# controller_board.net
KiCad netlist of a schematic drawn in EAGLE
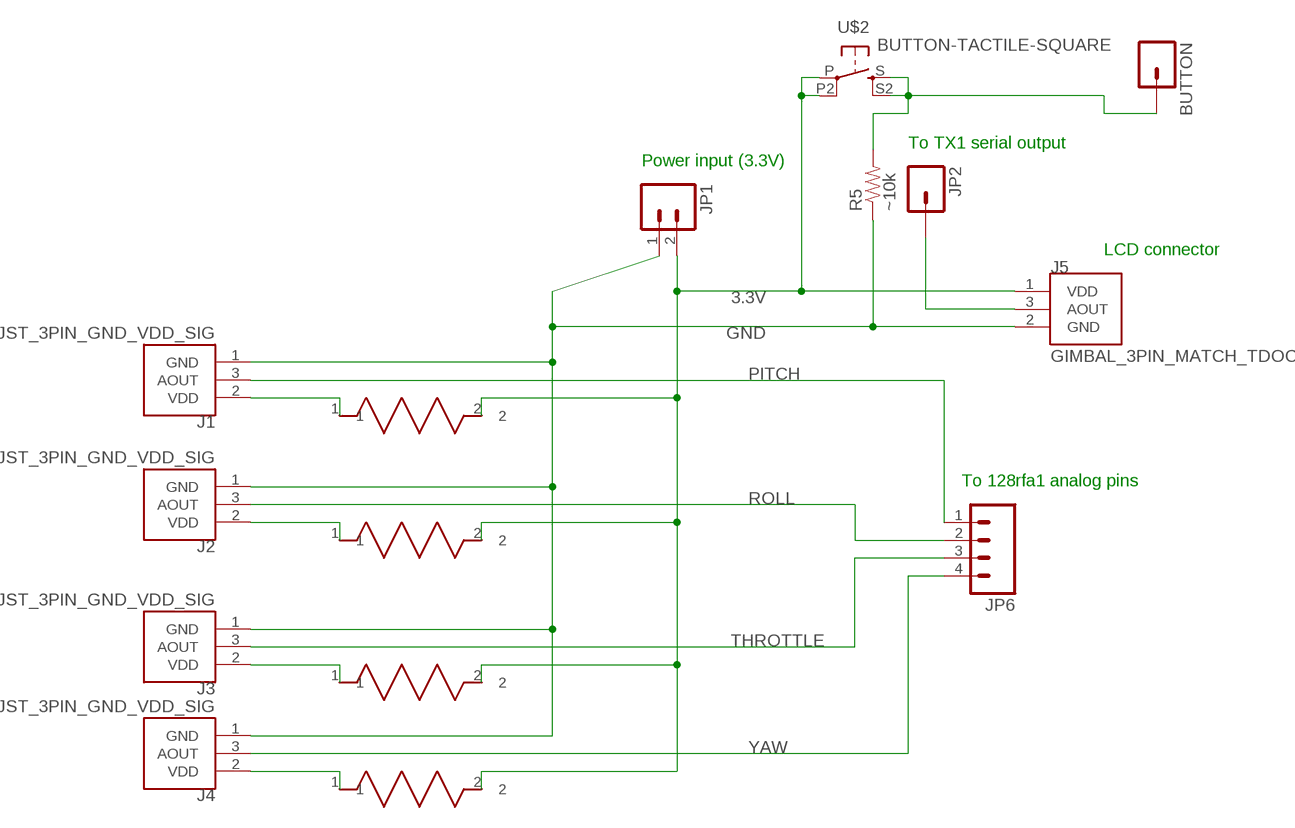
[diagram p0: schematic, sheet 1]

(export (version "E")
  (design (tool "Eeschema 10.0.6"))
  (components
    (comp (ref "BUTTON")
      (value "M01PTH")
      (footprint "eagle-import:1X01")
      (libsource (lib "eagle-import") (part "M01PTH"))
    )
    (comp (ref "J1")
      (value "JST_3PIN_GND_VDD_SIG")
      (footprint "eagle-import:JST-3-PTH-REVERSE")
      (libsource (lib "eagle-import") (part "JST_3PIN_GND_VDD_SIG"))
    )
    (comp (ref "J2")
      (value "JST_3PIN_GND_VDD_SIG")
      (footprint "eagle-import:JST-3-PTH-REVERSE")
      (libsource (lib "eagle-import") (part "JST_3PIN_GND_VDD_SIG"))
    )
    (comp (ref "J3")
      (value "JST_3PIN_GND_VDD_SIG")
      (footprint "eagle-import:JST-3-PTH-REVERSE")
      (libsource (lib "eagle-import") (part "JST_3PIN_GND_VDD_SIG"))
    )
    (comp (ref "J4")
      (value "JST_3PIN_GND_VDD_SIG")
      (footprint "eagle-import:JST-3-PTH-REVERSE")
      (libsource (lib "eagle-import") (part "JST_3PIN_GND_VDD_SIG"))
    )
    (comp (ref "J5")
      (value "GIMBAL_3PIN_MATCH_TDOCU")
      (footprint "eagle-import:JST-3-PTH")
      (libsource (lib "eagle-import") (part "GIMBAL_3PIN_MATCH_TDOCU"))
    )
    (comp (ref "JP1")
      (value "M021X02_NO_SILK")
      (footprint "eagle-import:1X02_NO_SILK")
      (libsource (lib "eagle-import") (part "M021X02_NO_SILK"))
    )
    (comp (ref "JP2")
      (value "M01PTH")
      (footprint "eagle-import:1X01")
      (libsource (lib "eagle-import") (part "M01PTH"))
    )
    (comp (ref "JP6")
      (value "M04PTH")
      (footprint "eagle-import:1X04")
      (libsource (lib "eagle-import") (part "M04PTH"))
    )
    (comp (ref "PITCH")
      (value "2.5k")
      (footprint "eagle-import:RES_CRF12")
      (libsource (lib "eagle-import") (part "RES_CRF12"))
    )
    (comp (ref "R5")
      (value "~10k")
      (footprint "eagle-import:AXIAL-0.4")
      (libsource (lib "eagle-import") (part "RESISTORPTH-1/4W"))
    )
    (comp (ref "ROLL")
      (value "2.5k")
      (footprint "eagle-import:RES_CRF12")
      (libsource (lib "eagle-import") (part "RES_CRF12"))
    )
    (comp (ref "THROTTLE")
      (value "2.5k")
      (footprint "eagle-import:RES_CRF12")
      (libsource (lib "eagle-import") (part "RES_CRF12"))
    )
    (comp (ref "U$2")
      (value "BUTTON-TACTILE-SQUARE")
      (footprint "eagle-import:BUTTON-TACTILE-SQUARE-ADAFRUIT1010")
      (libsource (lib "eagle-import") (part "BUTTON-TACTILE-SQUARE"))
    )
    (comp (ref "YAW")
      (value "2.5k")
      (footprint "eagle-import:RES_CRF12")
      (libsource (lib "eagle-import") (part "RES_CRF12"))
    )
  )
  (nets
    (net (code "1") (name "/3.3V") (class "Default")
      (node (ref "J5") (pin "1") (pinfunction "VDD_1") (pintype "power_in"))
      (node (ref "JP1") (pin "2") (pinfunction "2_2") (pintype "passive"))
      (node (ref "PITCH") (pin "2") (pinfunction "2_2") (pintype "bidirectional"))
      (node (ref "ROLL") (pin "2") (pinfunction "2_2") (pintype "bidirectional"))
      (node (ref "THROTTLE") (pin "2") (pinfunction "2_2") (pintype "bidirectional"))
      (node (ref "U$2") (pin "P") (pinfunction "P_P") (pintype "passive"))
      (node (ref "U$2") (pin "P2") (pinfunction "P1_P2") (pintype "passive"))
      (node (ref "YAW") (pin "2") (pinfunction "2_2") (pintype "bidirectional"))
    )
    (net (code "2") (name "/GND") (class "Default")
      (node (ref "J1") (pin "1") (pinfunction "GND_1") (pintype "power_in"))
      (node (ref "J2") (pin "1") (pinfunction "GND_1") (pintype "power_in"))
      (node (ref "J3") (pin "1") (pinfunction "GND_1") (pintype "power_in"))
      (node (ref "J4") (pin "1") (pinfunction "GND_1") (pintype "power_in"))
      (node (ref "J5") (pin "2") (pinfunction "GND_2") (pintype "power_in"))
      (node (ref "JP1") (pin "1") (pinfunction "1_1") (pintype "passive"))
      (node (ref "R5") (pin "P$1") (pinfunction "1_P$1") (pintype "passive"))
    )
    (net (code "3") (name "/PITCH") (class "Default")
      (node (ref "J1") (pin "3") (pinfunction "AOUT_3") (pintype "bidirectional"))
      (node (ref "JP6") (pin "1") (pinfunction "1_1") (pintype "passive"))
    )
    (net (code "4") (name "/ROLL") (class "Default")
      (node (ref "J2") (pin "3") (pinfunction "AOUT_3") (pintype "bidirectional"))
      (node (ref "JP6") (pin "2") (pinfunction "2_2") (pintype "passive"))
    )
    (net (code "5") (name "/THROTTLE") (class "Default")
      (node (ref "J3") (pin "3") (pinfunction "AOUT_3") (pintype "bidirectional"))
      (node (ref "JP6") (pin "3") (pinfunction "3_3") (pintype "passive"))
    )
    (net (code "6") (name "/YAW") (class "Default")
      (node (ref "J4") (pin "3") (pinfunction "AOUT_3") (pintype "bidirectional"))
      (node (ref "JP6") (pin "4") (pinfunction "4_4") (pintype "passive"))
    )
    (net (code "7") (name "Net-(J1-VDD)") (class "Default")
      (node (ref "J1") (pin "2") (pinfunction "VDD_2") (pintype "power_in"))
      (node (ref "PITCH") (pin "1") (pinfunction "1_1") (pintype "bidirectional"))
    )
    (net (code "8") (name "Net-(J2-VDD)") (class "Default")
      (node (ref "J2") (pin "2") (pinfunction "VDD_2") (pintype "power_in"))
      (node (ref "ROLL") (pin "1") (pinfunction "1_1") (pintype "bidirectional"))
    )
    (net (code "9") (name "Net-(J3-VDD)") (class "Default")
      (node (ref "J3") (pin "2") (pinfunction "VDD_2") (pintype "power_in"))
      (node (ref "THROTTLE") (pin "1") (pinfunction "1_1") (pintype "bidirectional"))
    )
    (net (code "10") (name "Net-(J4-VDD)") (class "Default")
      (node (ref "J4") (pin "2") (pinfunction "VDD_2") (pintype "power_in"))
      (node (ref "YAW") (pin "1") (pinfunction "1_1") (pintype "bidirectional"))
    )
    (net (code "11") (name "Net-(J5-AOUT)") (class "Default")
      (node (ref "J5") (pin "3") (pinfunction "AOUT_3") (pintype "bidirectional"))
      (node (ref "JP2") (pin "1") (pinfunction "1_1") (pintype "passive"))
    )
    (net (code "12") (name "Net-(R5-2)") (class "Default")
      (node (ref "BUTTON") (pin "1") (pinfunction "1_1") (pintype "passive"))
      (node (ref "R5") (pin "P$2") (pinfunction "2_P$2") (pintype "passive"))
      (node (ref "U$2") (pin "S") (pinfunction "S_S") (pintype "passive"))
      (node (ref "U$2") (pin "S2") (pinfunction "S1_S2") (pintype "passive"))
    )
  )
)
